# MicroLab.net
KiCad netlist of a schematic drawn in EAGLE
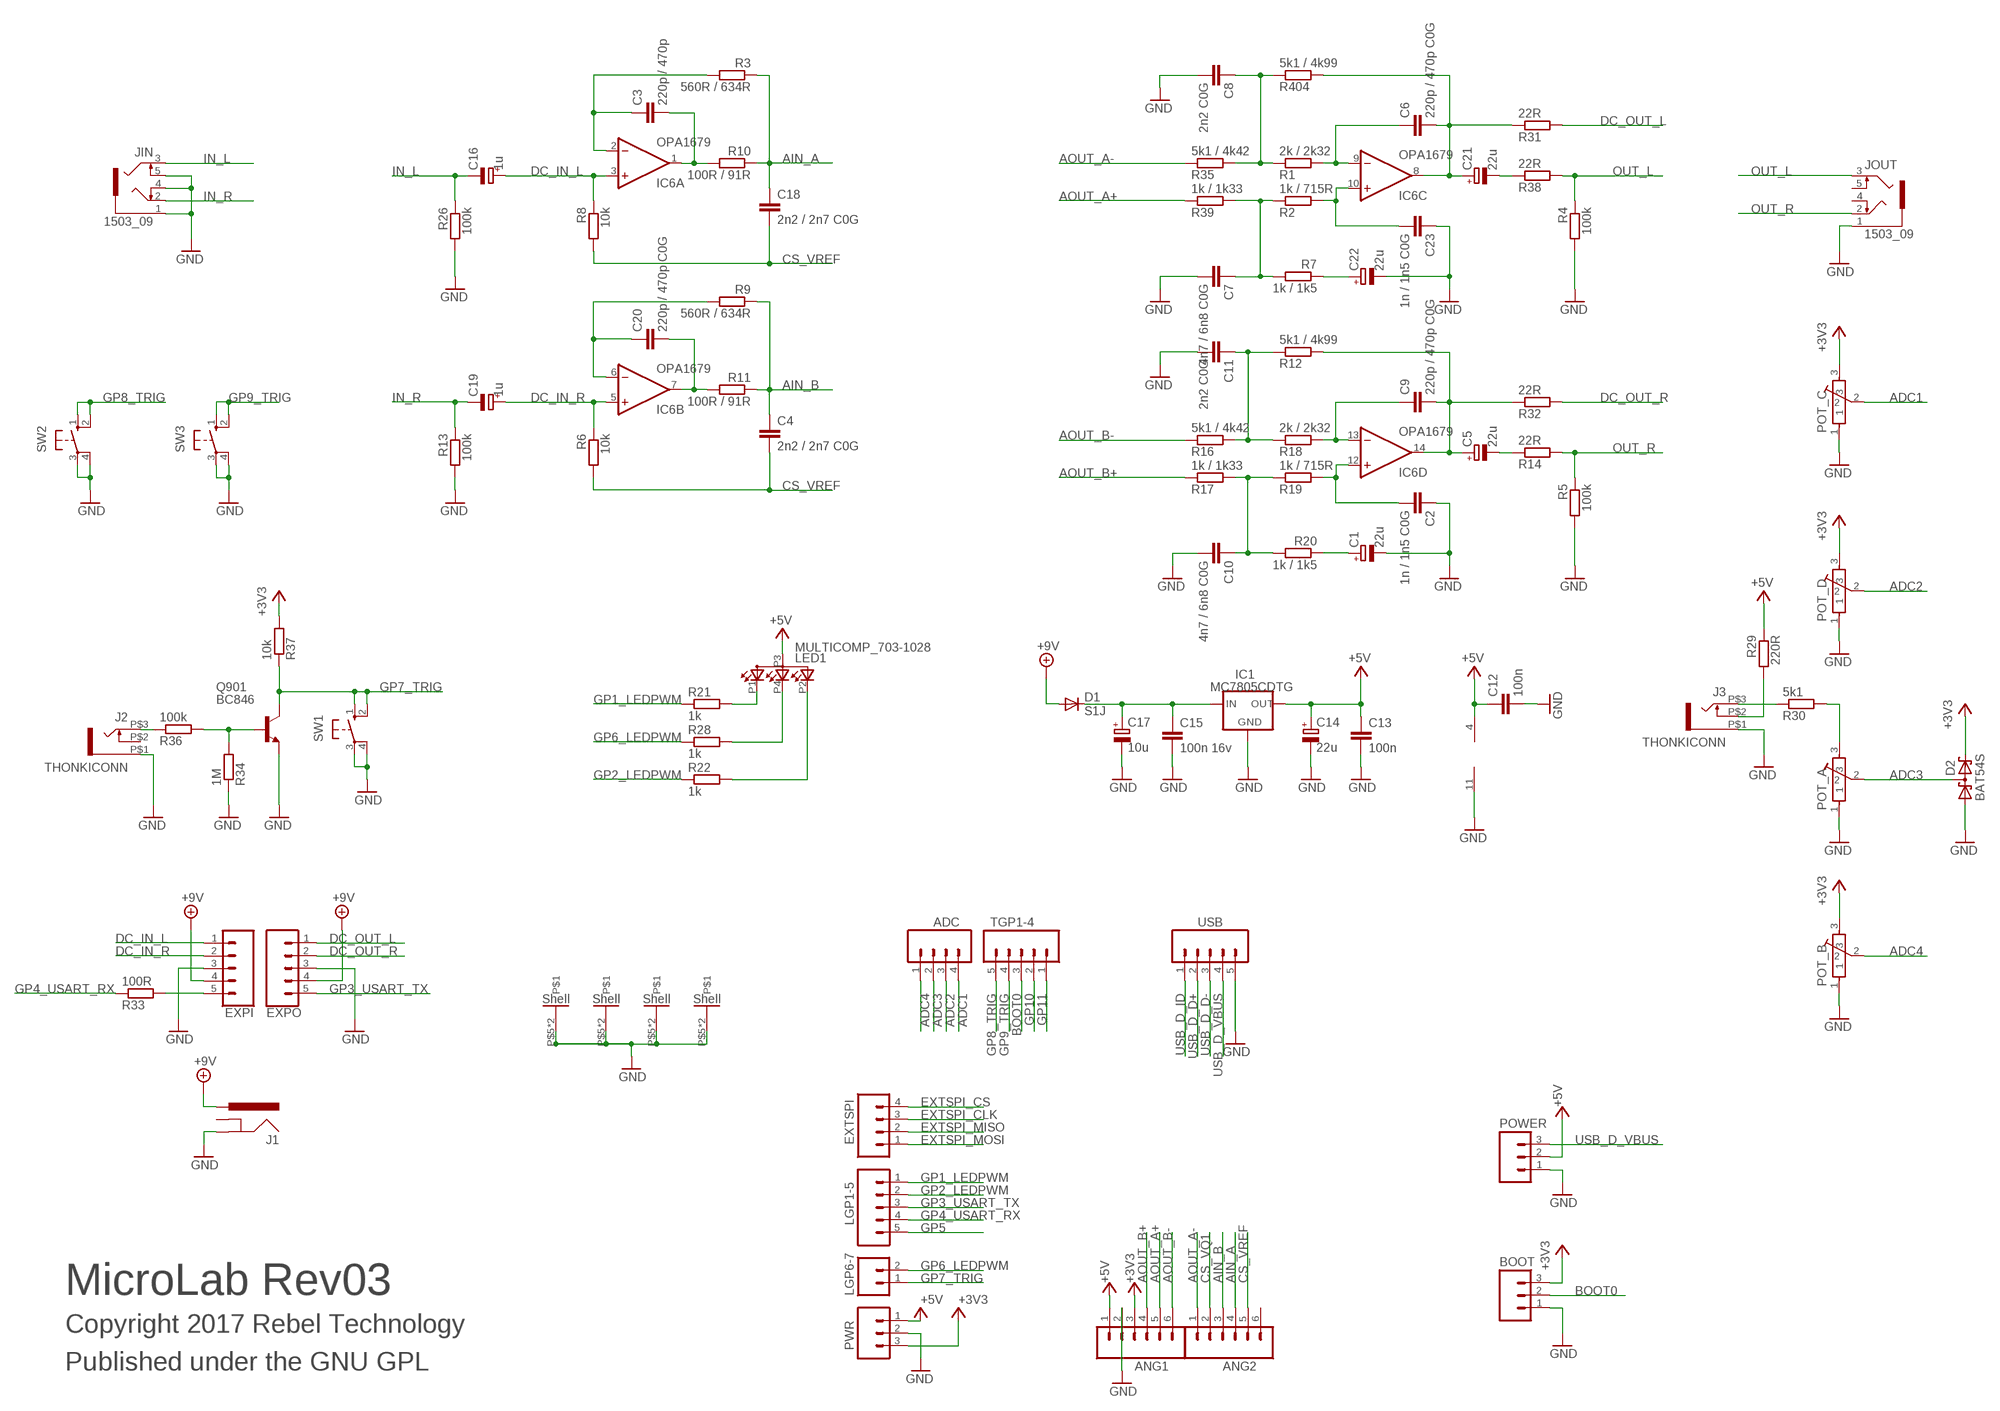
[diagram p0: schematic, sheet 1]

(export (version "E")
  (design (tool "Eeschema 10.0.6"))
  (components
    (comp (ref "ADC")
      (value "M04PTH")
      (footprint "eagle-import:1X04")
      (libsource (lib "eagle-import") (part "M04PTH"))
    )
    (comp (ref "ANG1")
      (value "M06SIP")
      (footprint "eagle-import:1X06")
      (libsource (lib "eagle-import") (part "M06SIP"))
    )
    (comp (ref "ANG2")
      (value "M06SIP")
      (footprint "eagle-import:1X06")
      (libsource (lib "eagle-import") (part "M06SIP"))
    )
    (comp (ref "BOOT")
      (value "M03PTH")
      (footprint "eagle-import:1X03")
      (libsource (lib "eagle-import") (part "M03PTH"))
    )
    (comp (ref "C1")
      (value "22u")
      (footprint "eagle-import:CPOL-5")
      (libsource (lib "eagle-import") (part "CPOL-EU153CLV-0505"))
    )
    (comp (ref "C2")
      (value "1n / 1n5 C0G")
      (footprint "eagle-import:C0603")
      (libsource (lib "eagle-import") (part "resistor_C-EUC0603"))
    )
    (comp (ref "C3")
      (value "220p / 470p")
      (footprint "eagle-import:C0603")
      (libsource (lib "eagle-import") (part "resistor_C-EUC0603"))
    )
    (comp (ref "C4")
      (value "2n2 / 2n7 C0G")
      (footprint "eagle-import:C0603")
      (libsource (lib "eagle-import") (part "resistor_C-EUC0603"))
    )
    (comp (ref "C5")
      (value "22u")
      (footprint "eagle-import:CPOL-5")
      (libsource (lib "eagle-import") (part "CPOL-EU153CLV-0505"))
    )
    (comp (ref "C6")
      (value "220p / 470p C0G")
      (footprint "eagle-import:C0603")
      (libsource (lib "eagle-import") (part "resistor_C-EUC0603"))
    )
    (comp (ref "C7")
      (value "4n7 / 6n8 C0G")
      (footprint "eagle-import:C0603")
      (libsource (lib "eagle-import") (part "resistor_C-EUC0603"))
    )
    (comp (ref "C8")
      (value "2n2 C0G")
      (footprint "eagle-import:C0603")
      (libsource (lib "eagle-import") (part "resistor_C-EUC0603"))
    )
    (comp (ref "C9")
      (value "220p / 470p C0G")
      (footprint "eagle-import:C0603")
      (libsource (lib "eagle-import") (part "resistor_C-EUC0603"))
    )
    (comp (ref "C10")
      (value "4n7 / 6n8 C0G")
      (footprint "eagle-import:C0603")
      (libsource (lib "eagle-import") (part "resistor_C-EUC0603"))
    )
    (comp (ref "C11")
      (value "2n2 C0G")
      (footprint "eagle-import:C0603")
      (libsource (lib "eagle-import") (part "resistor_C-EUC0603"))
    )
    (comp (ref "C12")
      (value "100n")
      (footprint "eagle-import:C0603")
      (libsource (lib "eagle-import") (part "resistor_C-EUC0603"))
    )
    (comp (ref "C13")
      (value "100n")
      (footprint "eagle-import:C0603")
      (libsource (lib "eagle-import") (part "C-EUC0603"))
    )
    (comp (ref "C14")
      (value "22u")
      (footprint "eagle-import:CPOL-5")
      (libsource (lib "eagle-import") (part "CPOL-EU153CLV-0505"))
    )
    (comp (ref "C15")
      (value "100n 16v")
      (footprint "eagle-import:C0603")
      (libsource (lib "eagle-import") (part "C-EUC0603"))
    )
    (comp (ref "C16")
      (value "1u")
      (footprint "eagle-import:153CLV-0405")
      (libsource (lib "eagle-import") (part "CPOL-EU153CLV-0405"))
    )
    (comp (ref "C17")
      (value "10u")
      (footprint "eagle-import:153CLV-0405")
      (libsource (lib "eagle-import") (part "CPOL-EU153CLV-0405"))
    )
    (comp (ref "C18")
      (value "2n2 / 2n7 C0G")
      (footprint "eagle-import:C0603")
      (libsource (lib "eagle-import") (part "resistor_C-EUC0603"))
    )
    (comp (ref "C19")
      (value "1u")
      (footprint "eagle-import:153CLV-0405")
      (libsource (lib "eagle-import") (part "CPOL-EU153CLV-0405"))
    )
    (comp (ref "C20")
      (value "220p / 470p C0G")
      (footprint "eagle-import:C0603")
      (libsource (lib "eagle-import") (part "resistor_C-EUC0603"))
    )
    (comp (ref "C21")
      (value "22u")
      (footprint "eagle-import:CPOL-5")
      (libsource (lib "eagle-import") (part "CPOL-EU153CLV-0505"))
    )
    (comp (ref "C22")
      (value "22u")
      (footprint "eagle-import:CPOL-5")
      (libsource (lib "eagle-import") (part "CPOL-EU153CLV-0505"))
    )
    (comp (ref "C23")
      (value "1n / 1n5 C0G")
      (footprint "eagle-import:C0603")
      (libsource (lib "eagle-import") (part "resistor_C-EUC0603"))
    )
    (comp (ref "D1")
      (value "S1J")
      (footprint "eagle-import:SMA-DIODE")
      (libsource (lib "eagle-import") (part "DIODESMA"))
    )
    (comp (ref "D2")
      (value "BAT54S")
      (footprint "eagle-import:SOT23")
      (libsource (lib "eagle-import") (part "BAT54S"))
    )
    (comp (ref "EXPI")
      (value "CONN_05JST-VERT")
      (footprint "eagle-import:JST-5-PTH-VERT")
      (libsource (lib "eagle-import") (part "CONN_05JST-VERT"))
    )
    (comp (ref "EXPO")
      (value "CONN_05JST-VERT")
      (footprint "eagle-import:JST-5-PTH-VERT")
      (libsource (lib "eagle-import") (part "CONN_05JST-VERT"))
    )
    (comp (ref "EXTSPI")
      (value "M04PTH")
      (footprint "eagle-import:1X04")
      (libsource (lib "eagle-import") (part "M04PTH"))
    )
    (comp (ref "IC1")
      (value "MC7805CDTG")
      (footprint "eagle-import:DPACK")
      (libsource (lib "eagle-import") (part "MC78XX"))
    )
    (comp (ref "IC6")
      (value "OPA1679")
      (footprint "eagle-import:SO14")
      (libsource (lib "eagle-import") (part "LM324D"))
    )
    (comp (ref "J1")
      (value "POWER_JACKPTH")
      (footprint "eagle-import:POWER_JACK_PTH")
      (libsource (lib "eagle-import") (part "POWER_JACKPTH"))
    )
    (comp (ref "J2")
      (value "THONKICONN")
      (footprint "eagle-import:THONKICONN")
      (libsource (lib "eagle-import") (part "THONKICONN"))
    )
    (comp (ref "J3")
      (value "THONKICONN")
      (footprint "eagle-import:THONKICONN")
      (libsource (lib "eagle-import") (part "THONKICONN"))
    )
    (comp (ref "JIN")
      (value "1503_09")
      (footprint "eagle-import:1503_09")
      (libsource (lib "eagle-import") (part "1503_09"))
    )
    (comp (ref "JOUT")
      (value "1503_09")
      (footprint "eagle-import:1503_09")
      (libsource (lib "eagle-import") (part "1503_09"))
    )
    (comp (ref "LED1")
      (value "MULTICOMP_703-1028")
      (footprint "eagle-import:RGB-LED-703-1028")
      (libsource (lib "eagle-import") (part "MULTICOMP_703-1028"))
    )
    (comp (ref "LGP1-5")
      (value "M05PTH")
      (footprint "eagle-import:1X05")
      (libsource (lib "eagle-import") (part "M05PTH"))
    )
    (comp (ref "LGP6-7")
      (value "M02PTH")
      (footprint "eagle-import:1X02")
      (libsource (lib "eagle-import") (part "M02PTH"))
    )
    (comp (ref "POT_A")
      (value "POT-ALPS-RK09L1140")
      (footprint "eagle-import:POT-ALPS-RK09L1140")
      (libsource (lib "eagle-import") (part "POT-ALPS-RK09L1140"))
    )
    (comp (ref "POT_B")
      (value "POT-ALPS-RK09L1140")
      (footprint "eagle-import:POT-ALPS-RK09L1140")
      (libsource (lib "eagle-import") (part "POT-ALPS-RK09L1140"))
    )
    (comp (ref "POT_C")
      (value "POT-ALPS-RK09L1140")
      (footprint "eagle-import:POT-ALPS-RK09L1140")
      (libsource (lib "eagle-import") (part "POT-ALPS-RK09L1140"))
    )
    (comp (ref "POT_D")
      (value "POT-ALPS-RK09L1140")
      (footprint "eagle-import:POT-ALPS-RK09L1140")
      (libsource (lib "eagle-import") (part "POT-ALPS-RK09L1140"))
    )
    (comp (ref "POWER")
      (value "M03PTH")
      (footprint "eagle-import:1X03")
      (libsource (lib "eagle-import") (part "M03PTH"))
    )
    (comp (ref "PWR")
      (value "M03PTH")
      (footprint "eagle-import:1X03")
      (libsource (lib "eagle-import") (part "M03PTH"))
    )
    (comp (ref "Q901")
      (value "BC846")
      (footprint "eagle-import:SOT23")
      (libsource (lib "eagle-import") (part "BC846"))
    )
    (comp (ref "R1")
      (value "2k / 2k32")
      (footprint "eagle-import:0603")
      (libsource (lib "eagle-import") (part "R-EU_0603"))
    )
    (comp (ref "R2")
      (value "1k / 715R")
      (footprint "eagle-import:0603")
      (libsource (lib "eagle-import") (part "R-EU_0603"))
    )
    (comp (ref "R3")
      (value "560R / 634R")
      (footprint "eagle-import:0603")
      (libsource (lib "eagle-import") (part "R-EU_0603"))
    )
    (comp (ref "R4")
      (value "100k")
      (footprint "eagle-import:0603")
      (libsource (lib "eagle-import") (part "R-EU_0603"))
    )
    (comp (ref "R5")
      (value "100k")
      (footprint "eagle-import:0603")
      (libsource (lib "eagle-import") (part "R-EU_0603"))
    )
    (comp (ref "R6")
      (value "10k")
      (footprint "eagle-import:0603")
      (libsource (lib "eagle-import") (part "R-EU_0603"))
    )
    (comp (ref "R7")
      (value "1k / 1k5")
      (footprint "eagle-import:0603")
      (libsource (lib "eagle-import") (part "R-EU_0603"))
    )
    (comp (ref "R8")
      (value "10k")
      (footprint "eagle-import:0603")
      (libsource (lib "eagle-import") (part "R-EU_0603"))
    )
    (comp (ref "R9")
      (value "560R / 634R")
      (footprint "eagle-import:0603")
      (libsource (lib "eagle-import") (part "R-EU_0603"))
    )
    (comp (ref "R10")
      (value "100R / 91R")
      (footprint "eagle-import:0603")
      (libsource (lib "eagle-import") (part "R-EU_0603"))
    )
    (comp (ref "R11")
      (value "100R / 91R")
      (footprint "eagle-import:0603")
      (libsource (lib "eagle-import") (part "R-EU_0603"))
    )
    (comp (ref "R12")
      (value "5k1 / 4k99")
      (footprint "eagle-import:0603")
      (libsource (lib "eagle-import") (part "R-EU_0603"))
    )
    (comp (ref "R13")
      (value "100k")
      (footprint "eagle-import:0603")
      (libsource (lib "eagle-import") (part "R-EU_0603"))
    )
    (comp (ref "R14")
      (value "22R")
      (footprint "eagle-import:0603")
      (libsource (lib "eagle-import") (part "R-EU_0603"))
    )
    (comp (ref "R16")
      (value "5k1 / 4k42")
      (footprint "eagle-import:0603")
      (libsource (lib "eagle-import") (part "R-EU_0603"))
    )
    (comp (ref "R17")
      (value "1k / 1k33")
      (footprint "eagle-import:0603")
      (libsource (lib "eagle-import") (part "R-EU_0603"))
    )
    (comp (ref "R18")
      (value "2k / 2k32")
      (footprint "eagle-import:0603")
      (libsource (lib "eagle-import") (part "R-EU_0603"))
    )
    (comp (ref "R19")
      (value "1k / 715R")
      (footprint "eagle-import:0603")
      (libsource (lib "eagle-import") (part "R-EU_0603"))
    )
    (comp (ref "R20")
      (value "1k / 1k5")
      (footprint "eagle-import:0603")
      (libsource (lib "eagle-import") (part "R-EU_0603"))
    )
    (comp (ref "R21")
      (value "1k")
      (footprint "eagle-import:0603")
      (libsource (lib "eagle-import") (part "R-EU_0603"))
    )
    (comp (ref "R22")
      (value "1k")
      (footprint "eagle-import:0603")
      (libsource (lib "eagle-import") (part "R-EU_0603"))
    )
    (comp (ref "R26")
      (value "100k")
      (footprint "eagle-import:0603")
      (libsource (lib "eagle-import") (part "R-EU_0603"))
    )
    (comp (ref "R28")
      (value "1k")
      (footprint "eagle-import:0603")
      (libsource (lib "eagle-import") (part "R-EU_0603"))
    )
    (comp (ref "R29")
      (value "220R")
      (footprint "eagle-import:0603")
      (libsource (lib "eagle-import") (part "R-EU_0603"))
    )
    (comp (ref "R30")
      (value "5k1")
      (footprint "eagle-import:0603")
      (libsource (lib "eagle-import") (part "R-EU_0603"))
    )
    (comp (ref "R31")
      (value "22R")
      (footprint "eagle-import:0603")
      (libsource (lib "eagle-import") (part "R-EU_0603"))
    )
    (comp (ref "R32")
      (value "22R")
      (footprint "eagle-import:0603")
      (libsource (lib "eagle-import") (part "R-EU_0603"))
    )
    (comp (ref "R33")
      (value "100R")
      (footprint "eagle-import:0603")
      (libsource (lib "eagle-import") (part "R-EU_0603"))
    )
    (comp (ref "R34")
      (value "1M")
      (footprint "eagle-import:0603")
      (libsource (lib "eagle-import") (part "R-EU_0603"))
    )
    (comp (ref "R35")
      (value "5k1 / 4k42")
      (footprint "eagle-import:0603")
      (libsource (lib "eagle-import") (part "R-EU_0603"))
    )
    (comp (ref "R36")
      (value "100k")
      (footprint "eagle-import:0603")
      (libsource (lib "eagle-import") (part "R-EU_0603"))
    )
    (comp (ref "R37")
      (value "10k")
      (footprint "eagle-import:0603")
      (libsource (lib "eagle-import") (part "R-EU_0603"))
    )
    (comp (ref "R38")
      (value "22R")
      (footprint "eagle-import:0603")
      (libsource (lib "eagle-import") (part "R-EU_0603"))
    )
    (comp (ref "R39")
      (value "1k / 1k33")
      (footprint "eagle-import:0603")
      (libsource (lib "eagle-import") (part "R-EU_0603"))
    )
    (comp (ref "R404")
      (value "5k1 / 4k99")
      (footprint "eagle-import:0603")
      (libsource (lib "eagle-import") (part "R-EU_0603"))
    )
    (comp (ref "SW1")
      (value "10-XX")
      (footprint "eagle-import:B3F-10XX")
      (fields (field (name "MPN") "B3F-1000"))
      (libsource (lib "eagle-import") (part "10-XX"))
    )
    (comp (ref "SW2")
      (value "10-XX")
      (footprint "eagle-import:B3F-10XX")
      (fields (field (name "MPN") "B3F-1000"))
      (libsource (lib "eagle-import") (part "10-XX"))
    )
    (comp (ref "SW3")
      (value "10-XX")
      (footprint "eagle-import:B3F-10XX")
      (fields (field (name "MPN") "B3F-1000"))
      (libsource (lib "eagle-import") (part "10-XX"))
    )
    (comp (ref "TGP1-4")
      (value "M05PTH")
      (footprint "eagle-import:1X05")
      (libsource (lib "eagle-import") (part "M05PTH"))
    )
    (comp (ref "USB")
      (value "M05PTH")
      (footprint "eagle-import:1X05")
      (libsource (lib "eagle-import") (part "M05PTH"))
    )
  )
  (nets
    (net (code "1") (name "+3V3") (class "Default")
      (node (ref "ANG1") (pin "3") (pinfunction "3_3") (pintype "passive"))
      (node (ref "BOOT") (pin "3") (pinfunction "3_3") (pintype "passive"))
      (node (ref "D2") (pin "2") (pinfunction "C2_2") (pintype "passive"))
      (node (ref "POT_B") (pin "3") (pinfunction "3_3") (pintype "bidirectional"))
      (node (ref "POT_C") (pin "3") (pinfunction "3_3") (pintype "bidirectional"))
      (node (ref "POT_D") (pin "3") (pinfunction "3_3") (pintype "bidirectional"))
      (node (ref "PWR") (pin "3") (pinfunction "3_3") (pintype "passive"))
      (node (ref "R37") (pin "2") (pinfunction "2_2") (pintype "passive"))
    )
    (net (code "2") (name "+5V") (class "Default")
      (node (ref "ANG1") (pin "1") (pinfunction "1_1") (pintype "passive"))
      (node (ref "C12") (pin "1") (pinfunction "1_1") (pintype "passive"))
      (node (ref "C13") (pin "1") (pinfunction "1_1") (pintype "passive"))
      (node (ref "C14") (pin "+") (pinfunction "+_+") (pintype "passive"))
      (node (ref "IC1") (pin "3") (pinfunction "OUT_3") (pintype "passive"))
      (node (ref "IC6") (pin "4") (pinfunction "V+_4") (pintype "power_in"))
      (node (ref "LED1") (pin "P3") (pinfunction "A_P3") (pintype "passive"))
      (node (ref "POWER") (pin "2") (pinfunction "2_2") (pintype "passive"))
      (node (ref "PWR") (pin "1") (pinfunction "1_1") (pintype "passive"))
      (node (ref "R29") (pin "1") (pinfunction "1_1") (pintype "passive"))
    )
    (net (code "3") (name "+9V") (class "Default")
      (node (ref "D1") (pin "A") (pinfunction "A_A") (pintype "passive"))
      (node (ref "EXPI") (pin "4") (pinfunction "4_4") (pintype "passive"))
      (node (ref "EXPO") (pin "4") (pinfunction "4_4") (pintype "passive"))
      (node (ref "J1") (pin "PWR") (pinfunction "PWR_PWR") (pintype "bidirectional"))
    )
    (net (code "4") (name "/ADC1") (class "Default")
      (node (ref "ADC") (pin "4") (pinfunction "4_4") (pintype "passive"))
      (node (ref "POT_C") (pin "2") (pinfunction "2_2") (pintype "bidirectional"))
    )
    (net (code "5") (name "/ADC2") (class "Default")
      (node (ref "ADC") (pin "3") (pinfunction "3_3") (pintype "passive"))
      (node (ref "POT_D") (pin "2") (pinfunction "2_2") (pintype "bidirectional"))
    )
    (net (code "6") (name "/ADC3") (class "Default")
      (node (ref "ADC") (pin "2") (pinfunction "2_2") (pintype "passive"))
      (node (ref "D2") (pin "3") (pinfunction "C1A2_3") (pintype "passive"))
      (node (ref "POT_A") (pin "2") (pinfunction "2_2") (pintype "bidirectional"))
    )
    (net (code "7") (name "/ADC4") (class "Default")
      (node (ref "ADC") (pin "1") (pinfunction "1_1") (pintype "passive"))
      (node (ref "POT_B") (pin "2") (pinfunction "2_2") (pintype "bidirectional"))
    )
    (net (code "8") (name "/AIN_A") (class "Default")
      (node (ref "ANG2") (pin "4") (pinfunction "4_4") (pintype "passive"))
      (node (ref "C18") (pin "1") (pinfunction "1_1") (pintype "passive"))
      (node (ref "R10") (pin "1") (pinfunction "1_1") (pintype "passive"))
      (node (ref "R3") (pin "1") (pinfunction "1_1") (pintype "passive"))
    )
    (net (code "9") (name "/AIN_B") (class "Default")
      (node (ref "ANG2") (pin "3") (pinfunction "3_3") (pintype "passive"))
      (node (ref "C4") (pin "1") (pinfunction "1_1") (pintype "passive"))
      (node (ref "R11") (pin "1") (pinfunction "1_1") (pintype "passive"))
      (node (ref "R9") (pin "1") (pinfunction "1_1") (pintype "passive"))
    )
    (net (code "10") (name "/AOUT_A+") (class "Default")
      (node (ref "ANG1") (pin "5") (pinfunction "5_5") (pintype "passive"))
      (node (ref "R39") (pin "1") (pinfunction "1_1") (pintype "passive"))
    )
    (net (code "11") (name "/AOUT_A-") (class "Default")
      (node (ref "ANG2") (pin "1") (pinfunction "1_1") (pintype "passive"))
      (node (ref "R35") (pin "1") (pinfunction "1_1") (pintype "passive"))
    )
    (net (code "12") (name "/AOUT_B+") (class "Default")
      (node (ref "ANG1") (pin "4") (pinfunction "4_4") (pintype "passive"))
      (node (ref "R17") (pin "1") (pinfunction "1_1") (pintype "passive"))
    )
    (net (code "13") (name "/AOUT_B-") (class "Default")
      (node (ref "ANG1") (pin "6") (pinfunction "6_6") (pintype "passive"))
      (node (ref "R16") (pin "1") (pinfunction "1_1") (pintype "passive"))
    )
    (net (code "14") (name "/BOOT0") (class "Default")
      (node (ref "BOOT") (pin "2") (pinfunction "2_2") (pintype "passive"))
      (node (ref "TGP1-4") (pin "3") (pinfunction "3_3") (pintype "passive"))
    )
    (net (code "15") (name "/CS_VQ1") (class "Default")
      (node (ref "ANG2") (pin "2") (pinfunction "2_2") (pintype "passive"))
    )
    (net (code "16") (name "/CS_VREF") (class "Default")
      (node (ref "ANG2") (pin "5") (pinfunction "5_5") (pintype "passive"))
      (node (ref "C18") (pin "2") (pinfunction "2_2") (pintype "passive"))
      (node (ref "C4") (pin "2") (pinfunction "2_2") (pintype "passive"))
      (node (ref "R6") (pin "2") (pinfunction "2_2") (pintype "passive"))
      (node (ref "R8") (pin "2") (pinfunction "2_2") (pintype "passive"))
    )
    (net (code "17") (name "/DC_IN_L") (class "Default")
      (node (ref "C16") (pin "+") (pinfunction "+_+") (pintype "passive"))
      (node (ref "EXPI") (pin "1") (pinfunction "1_1") (pintype "passive"))
      (node (ref "IC6") (pin "3") (pinfunction "+IN_3") (pintype "input"))
      (node (ref "R8") (pin "1") (pinfunction "1_1") (pintype "passive"))
    )
    (net (code "18") (name "/DC_IN_R") (class "Default")
      (node (ref "C19") (pin "+") (pinfunction "+_+") (pintype "passive"))
      (node (ref "EXPI") (pin "2") (pinfunction "2_2") (pintype "passive"))
      (node (ref "IC6") (pin "5") (pinfunction "+IN_5") (pintype "input"))
      (node (ref "R6") (pin "1") (pinfunction "1_1") (pintype "passive"))
    )
    (net (code "19") (name "/DC_OUT_L") (class "Default")
      (node (ref "EXPO") (pin "1") (pinfunction "1_1") (pintype "passive"))
      (node (ref "R31") (pin "2") (pinfunction "2_2") (pintype "passive"))
    )
    (net (code "20") (name "/DC_OUT_R") (class "Default")
      (node (ref "EXPO") (pin "2") (pinfunction "2_2") (pintype "passive"))
      (node (ref "R32") (pin "2") (pinfunction "2_2") (pintype "passive"))
    )
    (net (code "21") (name "/EXTSPI_CLK") (class "Default")
      (node (ref "EXTSPI") (pin "3") (pinfunction "3_3") (pintype "passive"))
    )
    (net (code "22") (name "/EXTSPI_CS") (class "Default")
      (node (ref "EXTSPI") (pin "4") (pinfunction "4_4") (pintype "passive"))
    )
    (net (code "23") (name "/EXTSPI_MISO") (class "Default")
      (node (ref "EXTSPI") (pin "2") (pinfunction "2_2") (pintype "passive"))
    )
    (net (code "24") (name "/EXTSPI_MOSI") (class "Default")
      (node (ref "EXTSPI") (pin "1") (pinfunction "1_1") (pintype "passive"))
    )
    (net (code "25") (name "/GP1_LEDPWM") (class "Default")
      (node (ref "LGP1-5") (pin "1") (pinfunction "1_1") (pintype "passive"))
      (node (ref "R21") (pin "1") (pinfunction "1_1") (pintype "passive"))
    )
    (net (code "26") (name "/GP2_LEDPWM") (class "Default")
      (node (ref "LGP1-5") (pin "2") (pinfunction "2_2") (pintype "passive"))
      (node (ref "R22") (pin "1") (pinfunction "1_1") (pintype "passive"))
    )
    (net (code "27") (name "/GP3_USART_TX") (class "Default")
      (node (ref "EXPO") (pin "5") (pinfunction "5_5") (pintype "passive"))
      (node (ref "LGP1-5") (pin "3") (pinfunction "3_3") (pintype "passive"))
    )
    (net (code "28") (name "/GP4_USART_RX") (class "Default")
      (node (ref "LGP1-5") (pin "4") (pinfunction "4_4") (pintype "passive"))
      (node (ref "R33") (pin "1") (pinfunction "1_1") (pintype "passive"))
    )
    (net (code "29") (name "/GP5") (class "Default")
      (node (ref "LGP1-5") (pin "5") (pinfunction "5_5") (pintype "passive"))
    )
    (net (code "30") (name "/GP6_LEDPWM") (class "Default")
      (node (ref "LGP6-7") (pin "2") (pinfunction "2_2") (pintype "passive"))
      (node (ref "R28") (pin "1") (pinfunction "1_1") (pintype "passive"))
    )
    (net (code "31") (name "/GP7_TRIG") (class "Default")
      (node (ref "LGP6-7") (pin "1") (pinfunction "1_1") (pintype "passive"))
      (node (ref "Q901") (pin "3") (pinfunction "C_3") (pintype "passive"))
      (node (ref "R37") (pin "1") (pinfunction "1_1") (pintype "passive"))
      (node (ref "SW1") (pin "1") (pinfunction "S_1") (pintype "passive"))
      (node (ref "SW1") (pin "2") (pinfunction "S1_2") (pintype "passive"))
    )
    (net (code "32") (name "/GP8_TRIG") (class "Default")
      (node (ref "SW2") (pin "1") (pinfunction "S_1") (pintype "passive"))
      (node (ref "SW2") (pin "2") (pinfunction "S1_2") (pintype "passive"))
      (node (ref "TGP1-4") (pin "5") (pinfunction "5_5") (pintype "passive"))
    )
    (net (code "33") (name "/GP9_TRIG") (class "Default")
      (node (ref "SW3") (pin "1") (pinfunction "S_1") (pintype "passive"))
      (node (ref "SW3") (pin "2") (pinfunction "S1_2") (pintype "passive"))
      (node (ref "TGP1-4") (pin "4") (pinfunction "4_4") (pintype "passive"))
    )
    (net (code "34") (name "/GP10") (class "Default")
      (node (ref "TGP1-4") (pin "2") (pinfunction "2_2") (pintype "passive"))
    )
    (net (code "35") (name "/GP11") (class "Default")
      (node (ref "TGP1-4") (pin "1") (pinfunction "1_1") (pintype "passive"))
    )
    (net (code "36") (name "/IN_L") (class "Default")
      (node (ref "C16") (pin "-") (pinfunction "-_-") (pintype "passive"))
      (node (ref "JIN") (pin "3") (pinfunction "3_3") (pintype "passive"))
      (node (ref "R26") (pin "1") (pinfunction "1_1") (pintype "passive"))
    )
    (net (code "37") (name "/IN_R") (class "Default")
      (node (ref "C19") (pin "-") (pinfunction "-_-") (pintype "passive"))
      (node (ref "JIN") (pin "2") (pinfunction "2_2") (pintype "passive"))
      (node (ref "R13") (pin "1") (pinfunction "1_1") (pintype "passive"))
    )
    (net (code "38") (name "/OUT_L") (class "Default")
      (node (ref "JOUT") (pin "3") (pinfunction "3_3") (pintype "passive"))
      (node (ref "R38") (pin "2") (pinfunction "2_2") (pintype "passive"))
      (node (ref "R4") (pin "1") (pinfunction "1_1") (pintype "passive"))
    )
    (net (code "39") (name "/OUT_R") (class "Default")
      (node (ref "JOUT") (pin "2") (pinfunction "2_2") (pintype "passive"))
      (node (ref "R14") (pin "2") (pinfunction "2_2") (pintype "passive"))
      (node (ref "R5") (pin "1") (pinfunction "1_1") (pintype "passive"))
    )
    (net (code "40") (name "/USB_D_D+") (class "Default")
      (node (ref "USB") (pin "2") (pinfunction "2_2") (pintype "passive"))
    )
    (net (code "41") (name "/USB_D_D-") (class "Default")
      (node (ref "USB") (pin "3") (pinfunction "3_3") (pintype "passive"))
    )
    (net (code "42") (name "/USB_D_ID") (class "Default")
      (node (ref "USB") (pin "1") (pinfunction "1_1") (pintype "passive"))
    )
    (net (code "43") (name "/USB_D_VBUS") (class "Default")
      (node (ref "POWER") (pin "3") (pinfunction "3_3") (pintype "passive"))
      (node (ref "USB") (pin "4") (pinfunction "4_4") (pintype "passive"))
    )
    (net (code "44") (name "GND") (class "Default")
      (node (ref "ANG1") (pin "2") (pinfunction "2_2") (pintype "passive"))
      (node (ref "BOOT") (pin "1") (pinfunction "1_1") (pintype "passive"))
      (node (ref "C1") (pin "-") (pinfunction "-_-") (pintype "passive"))
      (node (ref "C10") (pin "2") (pinfunction "2_2") (pintype "passive"))
      (node (ref "C11") (pin "2") (pinfunction "2_2") (pintype "passive"))
      (node (ref "C12") (pin "2") (pinfunction "2_2") (pintype "passive"))
      (node (ref "C13") (pin "2") (pinfunction "2_2") (pintype "passive"))
      (node (ref "C14") (pin "-") (pinfunction "-_-") (pintype "passive"))
      (node (ref "C15") (pin "2") (pinfunction "2_2") (pintype "passive"))
      (node (ref "C17") (pin "-") (pinfunction "-_-") (pintype "passive"))
      (node (ref "C2") (pin "1") (pinfunction "1_1") (pintype "passive"))
      (node (ref "C22") (pin "-") (pinfunction "-_-") (pintype "passive"))
      (node (ref "C23") (pin "1") (pinfunction "1_1") (pintype "passive"))
      (node (ref "C7") (pin "2") (pinfunction "2_2") (pintype "passive"))
      (node (ref "C8") (pin "2") (pinfunction "2_2") (pintype "passive"))
      (node (ref "D2") (pin "1") (pinfunction "A1_1") (pintype "passive"))
      (node (ref "EXPI") (pin "3") (pinfunction "3_3") (pintype "passive"))
      (node (ref "EXPO") (pin "3") (pinfunction "3_3") (pintype "passive"))
      (node (ref "IC1") (pin "4") (pinfunction "GND_4") (pintype "input"))
      (node (ref "IC6") (pin "11") (pinfunction "V-_11") (pintype "power_in"))
      (node (ref "J1") (pin "GND") (pinfunction "GND_GND") (pintype "bidirectional"))
      (node (ref "J2") (pin "P$1") (pinfunction "5_P$1") (pintype "passive"))
      (node (ref "J3") (pin "P$1") (pinfunction "5_P$1") (pintype "passive"))
      (node (ref "JIN") (pin "1") (pinfunction "1_1") (pintype "passive"))
      (node (ref "JIN") (pin "4") (pinfunction "4_4") (pintype "passive"))
      (node (ref "JIN") (pin "5") (pinfunction "5_5") (pintype "passive"))
      (node (ref "JOUT") (pin "1") (pinfunction "1_1") (pintype "passive"))
      (node (ref "POT_A") (pin "1") (pinfunction "1_1") (pintype "bidirectional"))
      (node (ref "POT_A") (pin "P$5") (pinfunction "P$1_P$5") (pintype "bidirectional"))
      (node (ref "POT_A") (pin "P$6") (pinfunction "P$1_P$6") (pintype "bidirectional"))
      (node (ref "POT_B") (pin "1") (pinfunction "1_1") (pintype "bidirectional"))
      (node (ref "POT_B") (pin "P$5") (pinfunction "P$1_P$5") (pintype "bidirectional"))
      (node (ref "POT_B") (pin "P$6") (pinfunction "P$1_P$6") (pintype "bidirectional"))
      (node (ref "POT_C") (pin "1") (pinfunction "1_1") (pintype "bidirectional"))
      (node (ref "POT_C") (pin "P$5") (pinfunction "P$1_P$5") (pintype "bidirectional"))
      (node (ref "POT_C") (pin "P$6") (pinfunction "P$1_P$6") (pintype "bidirectional"))
      (node (ref "POT_D") (pin "1") (pinfunction "1_1") (pintype "bidirectional"))
      (node (ref "POT_D") (pin "P$5") (pinfunction "P$1_P$5") (pintype "bidirectional"))
      (node (ref "POT_D") (pin "P$6") (pinfunction "P$1_P$6") (pintype "bidirectional"))
      (node (ref "POWER") (pin "1") (pinfunction "1_1") (pintype "passive"))
      (node (ref "PWR") (pin "2") (pinfunction "2_2") (pintype "passive"))
      (node (ref "Q901") (pin "2") (pinfunction "E_2") (pintype "passive"))
      (node (ref "R13") (pin "2") (pinfunction "2_2") (pintype "passive"))
      (node (ref "R26") (pin "2") (pinfunction "2_2") (pintype "passive"))
      (node (ref "R34") (pin "1") (pinfunction "1_1") (pintype "passive"))
      (node (ref "R4") (pin "2") (pinfunction "2_2") (pintype "passive"))
      (node (ref "R5") (pin "2") (pinfunction "2_2") (pintype "passive"))
      (node (ref "SW1") (pin "3") (pinfunction "P_3") (pintype "passive"))
      (node (ref "SW1") (pin "4") (pinfunction "P1_4") (pintype "passive"))
      (node (ref "SW2") (pin "3") (pinfunction "P_3") (pintype "passive"))
      (node (ref "SW2") (pin "4") (pinfunction "P1_4") (pintype "passive"))
      (node (ref "SW3") (pin "3") (pinfunction "P_3") (pintype "passive"))
      (node (ref "SW3") (pin "4") (pinfunction "P1_4") (pintype "passive"))
      (node (ref "USB") (pin "5") (pinfunction "5_5") (pintype "passive"))
    )
    (net (code "45") (name "Net-(C1-Pad+)") (class "Default")
      (node (ref "C1") (pin "+") (pinfunction "+_+") (pintype "passive"))
      (node (ref "R20") (pin "1") (pinfunction "1_1") (pintype "passive"))
    )
    (net (code "46") (name "Net-(C5-Pad-)") (class "Default")
      (node (ref "C5") (pin "-") (pinfunction "-_-") (pintype "passive"))
      (node (ref "R14") (pin "1") (pinfunction "1_1") (pintype "passive"))
    )
    (net (code "47") (name "Net-(C7-Pad1)") (class "Default")
      (node (ref "C7") (pin "1") (pinfunction "1_1") (pintype "passive"))
      (node (ref "R2") (pin "1") (pinfunction "1_1") (pintype "passive"))
      (node (ref "R39") (pin "2") (pinfunction "2_2") (pintype "passive"))
      (node (ref "R7") (pin "2") (pinfunction "2_2") (pintype "passive"))
    )
    (net (code "48") (name "Net-(C8-Pad1)") (class "Default")
      (node (ref "C8") (pin "1") (pinfunction "1_1") (pintype "passive"))
      (node (ref "R1") (pin "1") (pinfunction "1_1") (pintype "passive"))
      (node (ref "R35") (pin "2") (pinfunction "2_2") (pintype "passive"))
      (node (ref "R404") (pin "1") (pinfunction "1_1") (pintype "passive"))
    )
    (net (code "49") (name "Net-(C10-Pad1)") (class "Default")
      (node (ref "C10") (pin "1") (pinfunction "1_1") (pintype "passive"))
      (node (ref "R17") (pin "2") (pinfunction "2_2") (pintype "passive"))
      (node (ref "R19") (pin "1") (pinfunction "1_1") (pintype "passive"))
      (node (ref "R20") (pin "2") (pinfunction "2_2") (pintype "passive"))
    )
    (net (code "50") (name "Net-(C11-Pad1)") (class "Default")
      (node (ref "C11") (pin "1") (pinfunction "1_1") (pintype "passive"))
      (node (ref "R12") (pin "1") (pinfunction "1_1") (pintype "passive"))
      (node (ref "R16") (pin "2") (pinfunction "2_2") (pintype "passive"))
      (node (ref "R18") (pin "1") (pinfunction "1_1") (pintype "passive"))
    )
    (net (code "51") (name "Net-(C21-Pad-)") (class "Default")
      (node (ref "C21") (pin "-") (pinfunction "-_-") (pintype "passive"))
      (node (ref "R38") (pin "1") (pinfunction "1_1") (pintype "passive"))
    )
    (net (code "52") (name "Net-(C22-Pad+)") (class "Default")
      (node (ref "C22") (pin "+") (pinfunction "+_+") (pintype "passive"))
      (node (ref "R7") (pin "1") (pinfunction "1_1") (pintype "passive"))
    )
    (net (code "53") (name "Net-(EXPI-Pad5)") (class "Default")
      (node (ref "EXPI") (pin "5") (pinfunction "5_5") (pintype "passive"))
      (node (ref "R33") (pin "2") (pinfunction "2_2") (pintype "passive"))
    )
    (net (code "54") (name "Net-(IC1-IN)") (class "Default")
      (node (ref "C15") (pin "1") (pinfunction "1_1") (pintype "passive"))
      (node (ref "C17") (pin "+") (pinfunction "+_+") (pintype "passive"))
      (node (ref "D1") (pin "C") (pinfunction "C_C") (pintype "passive"))
      (node (ref "IC1") (pin "1") (pinfunction "IN_1") (pintype "input"))
    )
    (net (code "55") (name "Net-(IC6A--IN)") (class "Default")
      (node (ref "C3") (pin "1") (pinfunction "1_1") (pintype "passive"))
      (node (ref "IC6") (pin "2") (pinfunction "-IN_2") (pintype "input"))
      (node (ref "R3") (pin "2") (pinfunction "2_2") (pintype "passive"))
    )
    (net (code "56") (name "Net-(IC6A-OUT)") (class "Default")
      (node (ref "C3") (pin "2") (pinfunction "2_2") (pintype "passive"))
      (node (ref "IC6") (pin "1") (pinfunction "OUT_1") (pintype "output"))
      (node (ref "R10") (pin "2") (pinfunction "2_2") (pintype "passive"))
    )
    (net (code "57") (name "Net-(IC6B--IN)") (class "Default")
      (node (ref "C20") (pin "1") (pinfunction "1_1") (pintype "passive"))
      (node (ref "IC6") (pin "6") (pinfunction "-IN_6") (pintype "input"))
      (node (ref "R9") (pin "2") (pinfunction "2_2") (pintype "passive"))
    )
    (net (code "58") (name "Net-(IC6B-OUT)") (class "Default")
      (node (ref "C20") (pin "2") (pinfunction "2_2") (pintype "passive"))
      (node (ref "IC6") (pin "7") (pinfunction "OUT_7") (pintype "output"))
      (node (ref "R11") (pin "2") (pinfunction "2_2") (pintype "passive"))
    )
    (net (code "59") (name "Net-(IC6C-+IN)") (class "Default")
      (node (ref "C23") (pin "2") (pinfunction "2_2") (pintype "passive"))
      (node (ref "IC6") (pin "10") (pinfunction "+IN_10") (pintype "input"))
      (node (ref "R2") (pin "2") (pinfunction "2_2") (pintype "passive"))
    )
    (net (code "60") (name "Net-(IC6C--IN)") (class "Default")
      (node (ref "C6") (pin "1") (pinfunction "1_1") (pintype "passive"))
      (node (ref "IC6") (pin "9") (pinfunction "-IN_9") (pintype "input"))
      (node (ref "R1") (pin "2") (pinfunction "2_2") (pintype "passive"))
    )
    (net (code "61") (name "Net-(IC6C-OUT)") (class "Default")
      (node (ref "C21") (pin "+") (pinfunction "+_+") (pintype "passive"))
      (node (ref "C6") (pin "2") (pinfunction "2_2") (pintype "passive"))
      (node (ref "IC6") (pin "8") (pinfunction "OUT_8") (pintype "output"))
      (node (ref "R31") (pin "1") (pinfunction "1_1") (pintype "passive"))
      (node (ref "R404") (pin "2") (pinfunction "2_2") (pintype "passive"))
    )
    (net (code "62") (name "Net-(IC6D-+IN)") (class "Default")
      (node (ref "C2") (pin "2") (pinfunction "2_2") (pintype "passive"))
      (node (ref "IC6") (pin "12") (pinfunction "+IN_12") (pintype "input"))
      (node (ref "R19") (pin "2") (pinfunction "2_2") (pintype "passive"))
    )
    (net (code "63") (name "Net-(IC6D--IN)") (class "Default")
      (node (ref "C9") (pin "1") (pinfunction "1_1") (pintype "passive"))
      (node (ref "IC6") (pin "13") (pinfunction "-IN_13") (pintype "input"))
      (node (ref "R18") (pin "2") (pinfunction "2_2") (pintype "passive"))
    )
    (net (code "64") (name "Net-(IC6D-OUT)") (class "Default")
      (node (ref "C5") (pin "+") (pinfunction "+_+") (pintype "passive"))
      (node (ref "C9") (pin "2") (pinfunction "2_2") (pintype "passive"))
      (node (ref "IC6") (pin "14") (pinfunction "OUT_14") (pintype "output"))
      (node (ref "R12") (pin "2") (pinfunction "2_2") (pintype "passive"))
      (node (ref "R32") (pin "1") (pinfunction "1_1") (pintype "passive"))
    )
    (net (code "65") (name "Net-(J2-3)") (class "Default")
      (node (ref "J2") (pin "P$3") (pinfunction "3_P$3") (pintype "passive"))
      (node (ref "R36") (pin "1") (pinfunction "1_1") (pintype "passive"))
    )
    (net (code "66") (name "Net-(J3-3)") (class "Default")
      (node (ref "J3") (pin "P$3") (pinfunction "3_P$3") (pintype "passive"))
      (node (ref "R30") (pin "1") (pinfunction "1_1") (pintype "passive"))
    )
    (net (code "67") (name "Net-(J3-4)") (class "Default")
      (node (ref "J3") (pin "P$2") (pinfunction "4_P$2") (pintype "passive"))
      (node (ref "R29") (pin "2") (pinfunction "2_2") (pintype "passive"))
    )
    (net (code "68") (name "Net-(LED1-CBLUE)") (class "Default")
      (node (ref "LED1") (pin "P4") (pinfunction "CBLUE_P4") (pintype "passive"))
      (node (ref "R28") (pin "2") (pinfunction "2_2") (pintype "passive"))
    )
    (net (code "69") (name "Net-(LED1-CGREEN)") (class "Default")
      (node (ref "LED1") (pin "P2") (pinfunction "CGREEN_P2") (pintype "passive"))
      (node (ref "R22") (pin "2") (pinfunction "2_2") (pintype "passive"))
    )
    (net (code "70") (name "Net-(LED1-CRED)") (class "Default")
      (node (ref "LED1") (pin "P1") (pinfunction "CRED_P1") (pintype "passive"))
      (node (ref "R21") (pin "2") (pinfunction "2_2") (pintype "passive"))
    )
    (net (code "71") (name "Net-(POT_A-Pad3)") (class "Default")
      (node (ref "POT_A") (pin "3") (pinfunction "3_3") (pintype "bidirectional"))
      (node (ref "R30") (pin "2") (pinfunction "2_2") (pintype "passive"))
    )
    (net (code "72") (name "Net-(Q901-B)") (class "Default")
      (node (ref "Q901") (pin "1") (pinfunction "B_1") (pintype "passive"))
      (node (ref "R34") (pin "2") (pinfunction "2_2") (pintype "passive"))
      (node (ref "R36") (pin "2") (pinfunction "2_2") (pintype "passive"))
    )
    (net (code "73") (name "unconnected-(ANG2-Pad6)") (class "Default")
      (node (ref "ANG2") (pin "6") (pinfunction "6_6") (pintype "passive"))
    )
    (net (code "74") (name "unconnected-(J1-PadGNDBREAK)") (class "Default")
      (node (ref "J1") (pin "GNDBREAK") (pinfunction "GNDBREAK_GNDBREAK") (pintype "bidirectional"))
    )
    (net (code "75") (name "unconnected-(J2-4-PadP$2)") (class "Default")
      (node (ref "J2") (pin "P$2") (pinfunction "4_P$2") (pintype "passive"))
    )
    (net (code "76") (name "unconnected-(JOUT-Pad4)") (class "Default")
      (node (ref "JOUT") (pin "4") (pinfunction "4_4") (pintype "passive"))
    )
    (net (code "77") (name "unconnected-(JOUT-Pad5)") (class "Default")
      (node (ref "JOUT") (pin "5") (pinfunction "5_5") (pintype "passive"))
    )
  )
)
